# edp12.net
KiCad netlist of a schematic drawn in Altium Designer
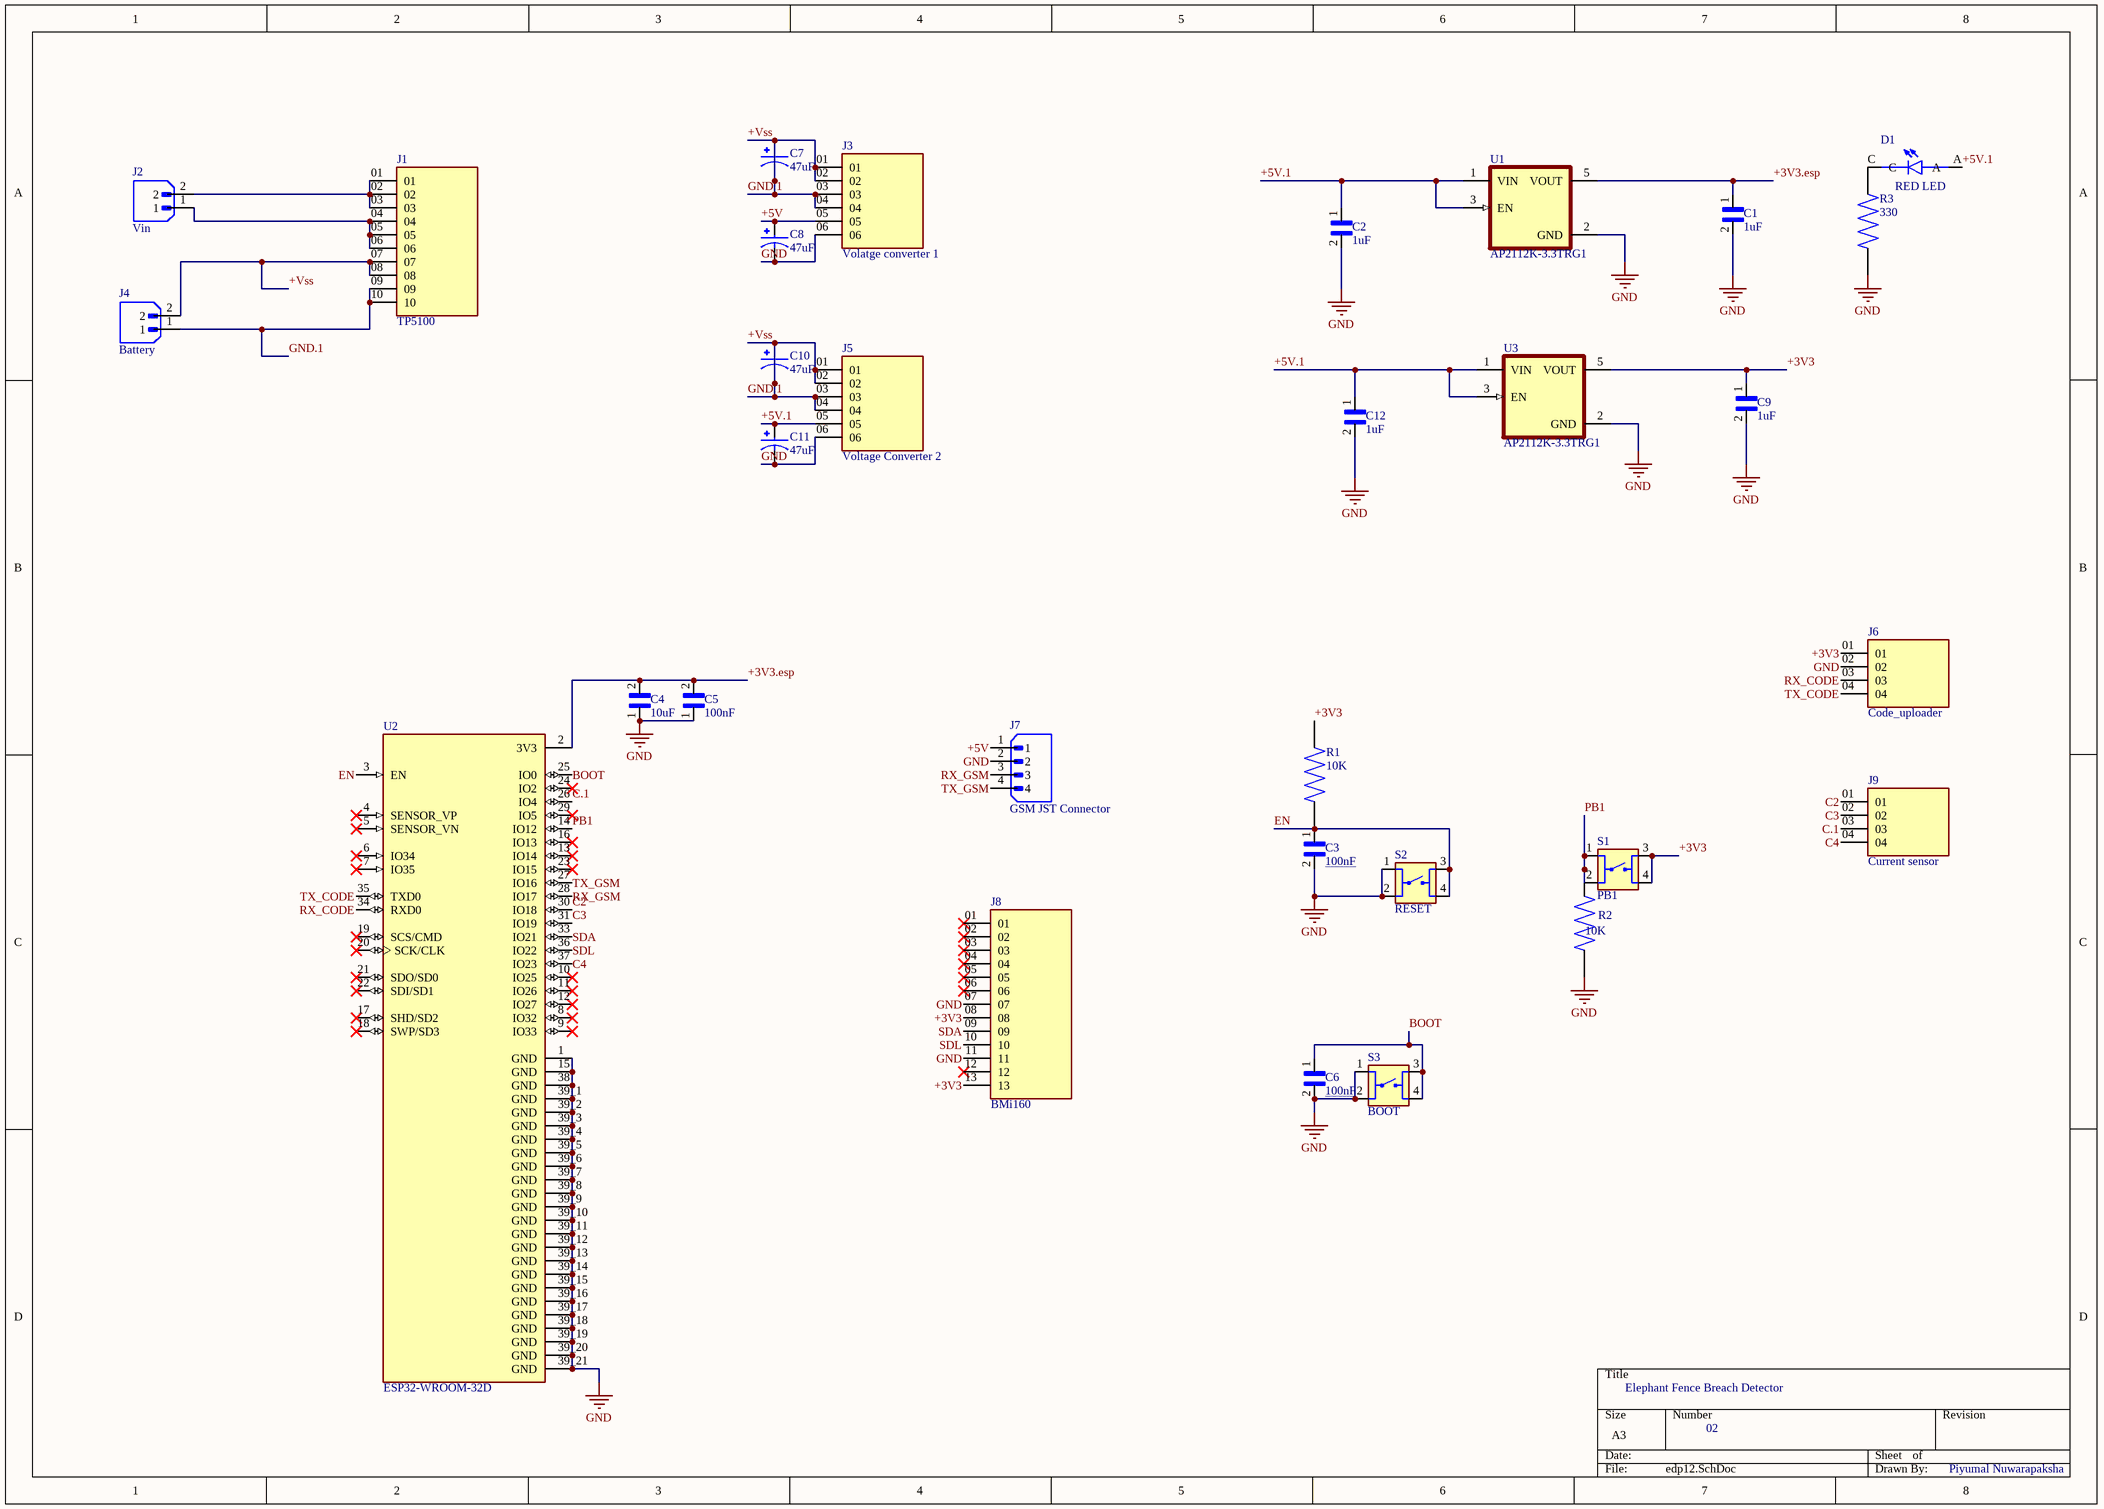
[diagram p0: edp12.SchDoc]

(export (version "E")
  (design (tool "Eeschema 10.0.6"))
  (components
    (comp (ref "C1")
      (value "1uF")
      (footprint "CAPC2012X135N")
      (description "Cap Ceramic 1uF 16V X7R 10% Pad SMD 0805 125C T/R")
      (fields (field (name "MP") "CL21B105KOFNNNE"))
      (libsource (lib "1uF") (part "CL21B105KOFNNNE"))
    )
    (comp (ref "C2")
      (value "1uF")
      (footprint "CAPC2012X135N")
      (description "Cap Ceramic 1uF 16V X7R 10% Pad SMD 0805 125C T/R")
      (fields (field (name "MP") "CL21B105KOFNNNE"))
      (libsource (lib "1uF") (part "CL21B105KOFNNNE"))
    )
    (comp (ref "C3")
      (value "CL31A106KBHNNNE")
      (footprint "CAPC2012X135N")
      (description "10ÂµF Â±10% 50V Ceramic Capacitor X5R 1206 (3216 Metric)")
      (fields (field (name "MF") "Samsung Electro-Mechanics") (field (name "ALTIUM_UNNAMED_1") "100nF"))
      (libsource (lib "10uF") (part "CL31A106KBHNNNE"))
    )
    (comp (ref "C4")
      (value "10uF")
      (footprint "CAPC2012X135N")
      (description "10ÂµF Â±10% 25V Ceramic Capacitor X5R 0805 (2012 Metric)")
      (fields (field (name "MF") "Samsung") (field (name "MP") "CL21A106KAYNNNE"))
      (libsource (lib "CL21A106KAYNNNE") (part "CL21A106KAYNNNE"))
    )
    (comp (ref "C5")
      (value "100nF")
      (footprint "CAPC2012X135N")
      (description "10ÂµF Â±10% 25V Ceramic Capacitor X5R 0805 (2012 Metric)")
      (fields (field (name "MF") "Samsung") (field (name "MP") "CL21A106KAYNNNE"))
      (libsource (lib "CL21A106KAYNNNE") (part "CL21A106KAYNNNE"))
    )
    (comp (ref "C6")
      (value "CL31A106KBHNNNE")
      (footprint "CAPC2012X135N")
      (description "10ÂµF Â±10% 50V Ceramic Capacitor X5R 1206 (3216 Metric)")
      (fields (field (name "MF") "Samsung Electro-Mechanics") (field (name "ALTIUM_UNNAMED_1") "100nF"))
      (libsource (lib "10uF") (part "CL31A106KBHNNNE"))
    )
    (comp (ref "C7")
      (value "47uF")
      (footprint "CAP_EEEFH1V470XL")
      (fields (field (name "MF") "Panasonic") (field (name "MP") "EEE-FH1V470XL"))
      (libsource (lib "47uF") (part "EEEFH1V470XL"))
    )
    (comp (ref "C8")
      (value "47uF")
      (footprint "CAP_EEEFH1V470XL")
      (fields (field (name "MF") "Panasonic") (field (name "MP") "EEE-FH1V470XL"))
      (libsource (lib "47uF") (part "EEEFH1V470XL"))
    )
    (comp (ref "C9")
      (value "1uF")
      (footprint "CAPC2012X135N")
      (description "Cap Ceramic 1uF 16V X7R 10% Pad SMD 0805 125C T/R")
      (fields (field (name "MP") "CL21B105KOFNNNE"))
      (libsource (lib "1uF") (part "CL21B105KOFNNNE"))
    )
    (comp (ref "C10")
      (value "47uF")
      (footprint "CAP_EEEFH1V470XL")
      (fields (field (name "MF") "Panasonic") (field (name "MP") "EEE-FH1V470XL"))
      (libsource (lib "47uF") (part "EEEFH1V470XL"))
    )
    (comp (ref "C11")
      (value "47uF")
      (footprint "CAP_EEEFH1V470XL")
      (fields (field (name "MF") "Panasonic") (field (name "MP") "EEE-FH1V470XL"))
      (libsource (lib "47uF") (part "EEEFH1V470XL"))
    )
    (comp (ref "C12")
      (value "1uF")
      (footprint "CAPC2012X135N")
      (description "Cap Ceramic 1uF 16V X7R 10% Pad SMD 0805 125C T/R")
      (fields (field (name "MP") "CL21B105KOFNNNE"))
      (libsource (lib "1uF") (part "CL21B105KOFNNNE"))
    )
    (comp (ref "D1")
      (value "RED LED")
      (footprint "LEDC2012X70N")
      (description "LED Uni-Color Green 4-Pin Chip 0805 T/R")
      (fields (field (name "MP") "597-3305-607F"))
      (libsource (lib "597-3305-607F (1)") (part "597-3305-607F"))
    )
    (comp (ref "J1")
      (value "TP5100")
      (footprint "SAMTEC_TS-121-G-AA")
      (description "Connector Header position")
      (fields (field (name "MP") "TS-121-G-AA") (field (name "MF") "Samtec"))
      (libsource (lib "power_header") (part "TS-121-G-AA"))
    )
    (comp (ref "J2")
      (value "Vin")
      (footprint "JST_B2B-XH-A(LF)(SN)")
      (description "Connector Header Through Hole 2 position 0.098 (2.50mm)")
      (fields (field (name "MF") "JST Sales") (field (name "MP") "B2B-XH-A(LF)(SN)"))
      (libsource (lib "B2B-XH-A_LF__SN_") (part "B2B-XH-A(LF)(SN)"))
    )
    (comp (ref "J3")
      (value "Volatge converter 1")
      (footprint "SAMTEC_TS-121-G-AA")
      (description "Connector Header position")
      (fields (field (name "MP") "TS-121-G-AA") (field (name "MF") "Samtec"))
      (libsource (lib "MD1584") (part "TS-121-G-AA"))
    )
    (comp (ref "J4")
      (value "Battery")
      (footprint "JST_B2B-XH-A(LF)(SN)")
      (description "Connector Header Through Hole 2 position 0.098 (2.50mm)")
      (fields (field (name "MF") "JST Sales") (field (name "MP") "B2B-XH-A(LF)(SN)"))
      (libsource (lib "B2B-XH-A_LF__SN_") (part "B2B-XH-A(LF)(SN)"))
    )
    (comp (ref "J5")
      (value "Voltage Converter 2")
      (footprint "SAMTEC_TS-121-G-AA")
      (description "Connector Header position")
      (fields (field (name "MP") "TS-121-G-AA") (field (name "MF") "Samtec"))
      (libsource (lib "MD1584") (part "TS-121-G-AA"))
    )
    (comp (ref "J6")
      (value "Code_uploader")
      (footprint "SAMTEC_TS-115-G-AA")
      (fields (field (name "MP") "TS-115-G-AA") (field (name "MF") "Samtec"))
      (libsource (lib "4pin_maleheader") (part "TS-115-G-AA"))
    )
    (comp (ref "J7")
      (value "GSM JST Connector")
      (footprint "JST_B4B-XH-A(LF)(SN)")
      (description "Connector Header Through Hole 4 position 0.098 (2.50mm)")
      (fields (field (name "MF") "JST Sales") (field (name "MP") "B4B-XH-A(LF)(SN)"))
      (libsource (lib "B4B-XH-A_LF__SN_") (part "B4B-XH-A(LF)(SN)"))
    )
    (comp (ref "J8")
      (value "BMi160")
      (footprint "SAMTEC_TS-115-G-AA")
      (fields (field (name "MP") "TS-115-G-AA") (field (name "MF") "Samtec"))
      (libsource (lib "BMImodule") (part "TS-115-G-AA"))
    )
    (comp (ref "J9")
      (value "Current sensor")
      (footprint "SAMTEC_TS-115-G-AA")
      (fields (field (name "MP") "TS-115-G-AA") (field (name "MF") "Samtec"))
      (libsource (lib "4pin_maleheader") (part "TS-115-G-AA"))
    )
    (comp (ref "R1")
      (value "10K")
      (footprint "RESC2012X60N")
      (description "10 kOhms Â±1% 0.125W, 1/8W Chip Resistor 0805 (2012 Metric) Moisture Resistant Thick Film")
      (fields (field (name "MF") "Yageo") (field (name "MP") "RC0805FR-0710KL"))
      (libsource (lib "10_k") (part "RC0805FR-0710KL"))
    )
    (comp (ref "R2")
      (value "10K")
      (footprint "RESC2012X60N")
      (description "10 kOhms Â±1% 0.125W, 1/8W Chip Resistor 0805 (2012 Metric) Moisture Resistant Thick Film")
      (fields (field (name "MF") "Yageo") (field (name "MP") "RC0805FR-0710KL"))
      (libsource (lib "10_k") (part "RC0805FR-0710KL"))
    )
    (comp (ref "R3")
      (value "330")
      (footprint "RESC2012X60N")
      (description "10 kOhms Â±1% 0.125W, 1/8W Chip Resistor 0805 (2012 Metric) Moisture Resistant Thick Film")
      (fields (field (name "MF") "Yageo") (field (name "MP") "RC0805FR-0710KL"))
      (libsource (lib "10_k") (part "RC0805FR-0710KL"))
    )
    (comp (ref "S1")
      (value "PB1")
      (footprint "SW_TS-1187A-B-A-B")
      (description "Tactile Switch SPST-NO Top Actuated Through Hole")
      (fields (field (name "MP") "FSM8JH") (field (name "MF") "TE Connectivity"))
      (libsource (lib "TS-1187A-B-A-B") (part "FSM8JH"))
    )
    (comp (ref "S2")
      (value "RESET")
      (footprint "SW_TS-1187A-B-A-B")
      (description "Tactile Switch SPST-NO Top Actuated Through Hole")
      (fields (field (name "MP") "FSM8JH") (field (name "MF") "TE Connectivity"))
      (libsource (lib "TS-1187A-B-A-B") (part "FSM8JH"))
    )
    (comp (ref "S3")
      (value "BOOT")
      (footprint "SW_TS-1187A-B-A-B")
      (description "Tactile Switch SPST-NO Top Actuated Through Hole")
      (fields (field (name "MP") "FSM8JH") (field (name "MF") "TE Connectivity"))
      (libsource (lib "TS-1187A-B-A-B") (part "FSM8JH"))
    )
    (comp (ref "U1")
      (value "AP2112K-3.3TRG1")
      (footprint "SOT95P285X140-5N")
      (description "Linear Voltage Regulator IC Positive Fixed 1 Output 600mA SOT-25")
      (fields (field (name "MF") "Diodes Inc."))
      (libsource (lib "AP2112K-3.3TRG1") (part "AP2112K-3.3TRG1"))
    )
    (comp (ref "U2")
      (value "ESP32-WROOM-32D")
      (footprint "MODULE_ESP32-WROOM-32D")
      (fields (field (name "MF") "Espressif Systems"))
      (libsource (lib "ESP32-WROOM-32D") (part "ESP32-WROOM-32D"))
    )
    (comp (ref "U3")
      (value "AP2112K-3.3TRG1")
      (footprint "SOT95P285X140-5N")
      (description "Linear Voltage Regulator IC Positive Fixed 1 Output 600mA SOT-25")
      (fields (field (name "MF") "Diodes Inc."))
      (libsource (lib "AP2112K-3.3TRG1") (part "AP2112K-3.3TRG1"))
    )
  )
  (nets
    (net (code "1") (name "/+3V3") (class "Default")
      (node (ref "C9") (pin "1") (pinfunction "1_1") (pintype "passive"))
      (node (ref "J6") (pin "01") (pinfunction "01_01") (pintype "passive"))
      (node (ref "J8") (pin "08") (pinfunction "08_08") (pintype "passive"))
      (node (ref "J8") (pin "13") (pinfunction "13_13") (pintype "passive"))
      (node (ref "R1") (pin "2") (pinfunction "2_2") (pintype "passive"))
      (node (ref "S1") (pin "3") (pinfunction "3_3") (pintype "passive"))
      (node (ref "S1") (pin "4") (pinfunction "4_4") (pintype "passive"))
      (node (ref "U3") (pin "5") (pinfunction "VOUT_5") (pintype "power_in"))
    )
    (net (code "2") (name "/+3V3.esp") (class "Default")
      (node (ref "C1") (pin "1") (pinfunction "1_1") (pintype "passive"))
      (node (ref "C4") (pin "2") (pinfunction "2_2") (pintype "passive"))
      (node (ref "C5") (pin "2") (pinfunction "2_2") (pintype "passive"))
      (node (ref "U1") (pin "5") (pinfunction "VOUT_5") (pintype "power_in"))
      (node (ref "U2") (pin "2") (pinfunction "3V3_2") (pintype "power_in"))
    )
    (net (code "3") (name "/+5V") (class "Default")
      (node (ref "C8") (pin "1") (pinfunction "1_1") (pintype "passive"))
      (node (ref "J3") (pin "05") (pinfunction "05_05") (pintype "passive"))
      (node (ref "J7") (pin "1") (pinfunction "1_1") (pintype "passive"))
    )
    (net (code "4") (name "/+5V.1") (class "Default")
      (node (ref "C11") (pin "1") (pinfunction "1_1") (pintype "passive"))
      (node (ref "C12") (pin "1") (pinfunction "1_1") (pintype "passive"))
      (node (ref "C2") (pin "1") (pinfunction "1_1") (pintype "passive"))
      (node (ref "D1") (pin "A") (pinfunction "A_A") (pintype "passive"))
      (node (ref "J5") (pin "05") (pinfunction "05_05") (pintype "passive"))
      (node (ref "U1") (pin "1") (pinfunction "VIN_1") (pintype "power_in"))
      (node (ref "U1") (pin "3") (pinfunction "EN_3") (pintype "input"))
      (node (ref "U3") (pin "1") (pinfunction "VIN_1") (pintype "power_in"))
      (node (ref "U3") (pin "3") (pinfunction "EN_3") (pintype "input"))
    )
    (net (code "5") (name "/+Vss") (class "Default")
      (node (ref "C10") (pin "1") (pinfunction "1_1") (pintype "passive"))
      (node (ref "C10") (pin "2") (pinfunction "2_2") (pintype "passive"))
      (node (ref "C7") (pin "1") (pinfunction "1_1") (pintype "passive"))
      (node (ref "C7") (pin "2") (pinfunction "2_2") (pintype "passive"))
      (node (ref "J1") (pin "07") (pinfunction "07_07") (pintype "passive"))
      (node (ref "J1") (pin "08") (pinfunction "08_08") (pintype "passive"))
      (node (ref "J1") (pin "09") (pinfunction "09_09") (pintype "passive"))
      (node (ref "J1") (pin "10") (pinfunction "10_10") (pintype "passive"))
      (node (ref "J3") (pin "01") (pinfunction "01_01") (pintype "passive"))
      (node (ref "J3") (pin "02") (pinfunction "02_02") (pintype "passive"))
      (node (ref "J3") (pin "03") (pinfunction "03_03") (pintype "passive"))
      (node (ref "J3") (pin "04") (pinfunction "04_04") (pintype "passive"))
      (node (ref "J4") (pin "1") (pinfunction "1_1") (pintype "passive"))
      (node (ref "J4") (pin "2") (pinfunction "2_2") (pintype "passive"))
      (node (ref "J5") (pin "01") (pinfunction "01_01") (pintype "passive"))
      (node (ref "J5") (pin "02") (pinfunction "02_02") (pintype "passive"))
      (node (ref "J5") (pin "03") (pinfunction "03_03") (pintype "passive"))
      (node (ref "J5") (pin "04") (pinfunction "04_04") (pintype "passive"))
    )
    (net (code "6") (name "/BOOT") (class "Default")
      (node (ref "C6") (pin "1") (pinfunction "1_1") (pintype "passive"))
      (node (ref "S3") (pin "3") (pinfunction "3_3") (pintype "passive"))
      (node (ref "S3") (pin "4") (pinfunction "4_4") (pintype "passive"))
      (node (ref "U2") (pin "25") (pinfunction "IO0_25") (pintype "bidirectional"))
    )
    (net (code "7") (name "/C.1") (class "Default")
      (node (ref "J9") (pin "03") (pinfunction "03_03") (pintype "passive"))
      (node (ref "U2") (pin "26") (pinfunction "IO4_26") (pintype "bidirectional"))
    )
    (net (code "8") (name "/C2") (class "Default")
      (node (ref "J9") (pin "01") (pinfunction "01_01") (pintype "passive"))
      (node (ref "U2") (pin "30") (pinfunction "IO18_30") (pintype "bidirectional"))
    )
    (net (code "9") (name "/C3") (class "Default")
      (node (ref "J9") (pin "02") (pinfunction "02_02") (pintype "passive"))
      (node (ref "U2") (pin "31") (pinfunction "IO19_31") (pintype "bidirectional"))
    )
    (net (code "10") (name "/C4") (class "Default")
      (node (ref "J9") (pin "04") (pinfunction "04_04") (pintype "passive"))
      (node (ref "U2") (pin "37") (pinfunction "IO23_37") (pintype "bidirectional"))
    )
    (net (code "11") (name "/EN") (class "Default")
      (node (ref "C3") (pin "1") (pinfunction "1_1") (pintype "passive"))
      (node (ref "R1") (pin "1") (pinfunction "1_1") (pintype "passive"))
      (node (ref "S2") (pin "3") (pinfunction "3_3") (pintype "passive"))
      (node (ref "S2") (pin "4") (pinfunction "4_4") (pintype "passive"))
      (node (ref "U2") (pin "3") (pinfunction "EN_3") (pintype "input"))
    )
    (net (code "12") (name "/PB1") (class "Default")
      (node (ref "R2") (pin "2") (pinfunction "2_2") (pintype "passive"))
      (node (ref "S1") (pin "1") (pinfunction "1_1") (pintype "passive"))
      (node (ref "S1") (pin "2") (pinfunction "2_2") (pintype "passive"))
      (node (ref "U2") (pin "14") (pinfunction "IO12_14") (pintype "bidirectional"))
    )
    (net (code "13") (name "/RX_CODE") (class "Default")
      (node (ref "J6") (pin "03") (pinfunction "03_03") (pintype "passive"))
      (node (ref "U2") (pin "34") (pinfunction "RXD0_34") (pintype "bidirectional"))
    )
    (net (code "14") (name "/RX_GSM") (class "Default")
      (node (ref "J7") (pin "3") (pinfunction "3_3") (pintype "passive"))
      (node (ref "U2") (pin "28") (pinfunction "IO17_28") (pintype "bidirectional"))
    )
    (net (code "15") (name "/SDA") (class "Default")
      (node (ref "J8") (pin "09") (pinfunction "09_09") (pintype "passive"))
      (node (ref "U2") (pin "33") (pinfunction "IO21_33") (pintype "bidirectional"))
    )
    (net (code "16") (name "/SDL") (class "Default")
      (node (ref "J8") (pin "10") (pinfunction "10_10") (pintype "passive"))
      (node (ref "U2") (pin "36") (pinfunction "IO22_36") (pintype "bidirectional"))
    )
    (net (code "17") (name "/TX_CODE") (class "Default")
      (node (ref "J6") (pin "04") (pinfunction "04_04") (pintype "passive"))
      (node (ref "U2") (pin "35") (pinfunction "TXD0_35") (pintype "bidirectional"))
    )
    (net (code "18") (name "/TX_GSM") (class "Default")
      (node (ref "J7") (pin "4") (pinfunction "4_4") (pintype "passive"))
      (node (ref "U2") (pin "27") (pinfunction "IO16_27") (pintype "bidirectional"))
    )
    (net (code "19") (name "GND") (class "Default")
      (node (ref "C1") (pin "2") (pinfunction "2_2") (pintype "passive"))
      (node (ref "C11") (pin "2") (pinfunction "2_2") (pintype "passive"))
      (node (ref "C12") (pin "2") (pinfunction "2_2") (pintype "passive"))
      (node (ref "C2") (pin "2") (pinfunction "2_2") (pintype "passive"))
      (node (ref "C3") (pin "2") (pinfunction "2_2") (pintype "passive"))
      (node (ref "C4") (pin "1") (pinfunction "1_1") (pintype "passive"))
      (node (ref "C5") (pin "1") (pinfunction "1_1") (pintype "passive"))
      (node (ref "C6") (pin "2") (pinfunction "2_2") (pintype "passive"))
      (node (ref "C8") (pin "2") (pinfunction "2_2") (pintype "passive"))
      (node (ref "C9") (pin "2") (pinfunction "2_2") (pintype "passive"))
      (node (ref "J3") (pin "06") (pinfunction "06_06") (pintype "passive"))
      (node (ref "J5") (pin "06") (pinfunction "06_06") (pintype "passive"))
      (node (ref "J6") (pin "02") (pinfunction "02_02") (pintype "passive"))
      (node (ref "J7") (pin "2") (pinfunction "2_2") (pintype "passive"))
      (node (ref "J8") (pin "07") (pinfunction "07_07") (pintype "passive"))
      (node (ref "J8") (pin "11") (pinfunction "11_11") (pintype "passive"))
      (node (ref "R2") (pin "1") (pinfunction "1_1") (pintype "passive"))
      (node (ref "R3") (pin "1") (pinfunction "1_1") (pintype "passive"))
      (node (ref "S2") (pin "1") (pinfunction "1_1") (pintype "passive"))
      (node (ref "S2") (pin "2") (pinfunction "2_2") (pintype "passive"))
      (node (ref "S3") (pin "1") (pinfunction "1_1") (pintype "passive"))
      (node (ref "S3") (pin "2") (pinfunction "2_2") (pintype "passive"))
      (node (ref "U1") (pin "2") (pinfunction "GND_2") (pintype "power_in"))
      (node (ref "U2") (pin "1") (pinfunction "GND_1") (pintype "power_in"))
      (node (ref "U2") (pin "15") (pinfunction "GND_15") (pintype "power_in"))
      (node (ref "U2") (pin "38") (pinfunction "GND_38") (pintype "power_in"))
      (node (ref "U2") (pin "39_1") (pinfunction "GND_39_1") (pintype "power_in"))
      (node (ref "U2") (pin "39_10") (pinfunction "GND_39_10") (pintype "power_in"))
      (node (ref "U2") (pin "39_11") (pinfunction "GND_39_11") (pintype "power_in"))
      (node (ref "U2") (pin "39_12") (pinfunction "GND_39_12") (pintype "power_in"))
      (node (ref "U2") (pin "39_13") (pinfunction "GND_39_13") (pintype "power_in"))
      (node (ref "U2") (pin "39_14") (pinfunction "GND_39_14") (pintype "power_in"))
      (node (ref "U2") (pin "39_15") (pinfunction "GND_39_15") (pintype "power_in"))
      (node (ref "U2") (pin "39_16") (pinfunction "GND_39_16") (pintype "power_in"))
      (node (ref "U2") (pin "39_17") (pinfunction "GND_39_17") (pintype "power_in"))
      (node (ref "U2") (pin "39_18") (pinfunction "GND_39_18") (pintype "power_in"))
      (node (ref "U2") (pin "39_19") (pinfunction "GND_39_19") (pintype "power_in"))
      (node (ref "U2") (pin "39_2") (pinfunction "GND_39_2") (pintype "power_in"))
      (node (ref "U2") (pin "39_20") (pinfunction "GND_39_20") (pintype "power_in"))
      (node (ref "U2") (pin "39_21") (pinfunction "GND_39_21") (pintype "power_in"))
      (node (ref "U2") (pin "39_3") (pinfunction "GND_39_3") (pintype "power_in"))
      (node (ref "U2") (pin "39_4") (pinfunction "GND_39_4") (pintype "power_in"))
      (node (ref "U2") (pin "39_5") (pinfunction "GND_39_5") (pintype "power_in"))
      (node (ref "U2") (pin "39_6") (pinfunction "GND_39_6") (pintype "power_in"))
      (node (ref "U2") (pin "39_7") (pinfunction "GND_39_7") (pintype "power_in"))
      (node (ref "U2") (pin "39_8") (pinfunction "GND_39_8") (pintype "power_in"))
      (node (ref "U2") (pin "39_9") (pinfunction "GND_39_9") (pintype "power_in"))
      (node (ref "U3") (pin "2") (pinfunction "GND_2") (pintype "power_in"))
    )
    (net (code "20") (name "Net-(D1-PadC)") (class "Default")
      (node (ref "D1") (pin "C") (pinfunction "C_C") (pintype "passive"))
      (node (ref "R3") (pin "2") (pinfunction "2_2") (pintype "passive"))
    )
    (net (code "21") (name "Net-(J1-Pad01)") (class "Default")
      (node (ref "J1") (pin "01") (pinfunction "01_01") (pintype "passive"))
      (node (ref "J1") (pin "02") (pinfunction "02_02") (pintype "passive"))
      (node (ref "J1") (pin "03") (pinfunction "03_03") (pintype "passive"))
      (node (ref "J2") (pin "2") (pinfunction "2_2") (pintype "passive"))
    )
    (net (code "22") (name "Net-(J1-Pad04)") (class "Default")
      (node (ref "J1") (pin "04") (pinfunction "04_04") (pintype "passive"))
      (node (ref "J1") (pin "05") (pinfunction "05_05") (pintype "passive"))
      (node (ref "J1") (pin "06") (pinfunction "06_06") (pintype "passive"))
      (node (ref "J2") (pin "1") (pinfunction "1_1") (pintype "passive"))
    )
    (net (code "23") (name "unconnected-(J8-Pad01)") (class "Default")
      (node (ref "J8") (pin "01") (pinfunction "01_01") (pintype "passive+no_connect"))
    )
    (net (code "24") (name "unconnected-(J8-Pad02)") (class "Default")
      (node (ref "J8") (pin "02") (pinfunction "02_02") (pintype "passive+no_connect"))
    )
    (net (code "25") (name "unconnected-(J8-Pad03)") (class "Default")
      (node (ref "J8") (pin "03") (pinfunction "03_03") (pintype "passive+no_connect"))
    )
    (net (code "26") (name "unconnected-(J8-Pad04)") (class "Default")
      (node (ref "J8") (pin "04") (pinfunction "04_04") (pintype "passive+no_connect"))
    )
    (net (code "27") (name "unconnected-(J8-Pad05)") (class "Default")
      (node (ref "J8") (pin "05") (pinfunction "05_05") (pintype "passive+no_connect"))
    )
    (net (code "28") (name "unconnected-(J8-Pad06)") (class "Default")
      (node (ref "J8") (pin "06") (pinfunction "06_06") (pintype "passive+no_connect"))
    )
    (net (code "29") (name "unconnected-(J8-Pad12)") (class "Default")
      (node (ref "J8") (pin "12") (pinfunction "12_12") (pintype "passive+no_connect"))
    )
    (net (code "30") (name "unconnected-(U2-IO2-Pad24)") (class "Default")
      (node (ref "U2") (pin "24") (pinfunction "IO2_24") (pintype "bidirectional+no_connect"))
    )
    (net (code "31") (name "unconnected-(U2-IO5-Pad29)") (class "Default")
      (node (ref "U2") (pin "29") (pinfunction "IO5_29") (pintype "bidirectional+no_connect"))
    )
    (net (code "32") (name "unconnected-(U2-IO13-Pad16)") (class "Default")
      (node (ref "U2") (pin "16") (pinfunction "IO13_16") (pintype "bidirectional+no_connect"))
    )
    (net (code "33") (name "unconnected-(U2-IO14-Pad13)") (class "Default")
      (node (ref "U2") (pin "13") (pinfunction "IO14_13") (pintype "bidirectional+no_connect"))
    )
    (net (code "34") (name "unconnected-(U2-IO15-Pad23)") (class "Default")
      (node (ref "U2") (pin "23") (pinfunction "IO15_23") (pintype "bidirectional+no_connect"))
    )
    (net (code "35") (name "unconnected-(U2-IO25-Pad10)") (class "Default")
      (node (ref "U2") (pin "10") (pinfunction "IO25_10") (pintype "bidirectional+no_connect"))
    )
    (net (code "36") (name "unconnected-(U2-IO26-Pad11)") (class "Default")
      (node (ref "U2") (pin "11") (pinfunction "IO26_11") (pintype "bidirectional+no_connect"))
    )
    (net (code "37") (name "unconnected-(U2-IO27-Pad12)") (class "Default")
      (node (ref "U2") (pin "12") (pinfunction "IO27_12") (pintype "bidirectional+no_connect"))
    )
    (net (code "38") (name "unconnected-(U2-IO32-Pad8)") (class "Default")
      (node (ref "U2") (pin "8") (pinfunction "IO32_8") (pintype "bidirectional+no_connect"))
    )
    (net (code "39") (name "unconnected-(U2-IO33-Pad9)") (class "Default")
      (node (ref "U2") (pin "9") (pinfunction "IO33_9") (pintype "bidirectional+no_connect"))
    )
    (net (code "40") (name "unconnected-(U2-IO34-Pad6)") (class "Default")
      (node (ref "U2") (pin "6") (pinfunction "IO34_6") (pintype "input+no_connect"))
    )
    (net (code "41") (name "unconnected-(U2-IO35-Pad7)") (class "Default")
      (node (ref "U2") (pin "7") (pinfunction "IO35_7") (pintype "input+no_connect"))
    )
    (net (code "42") (name "unconnected-(U2-SCK{slash}CLK-Pad20)") (class "Default")
      (node (ref "U2") (pin "20") (pinfunction "SCK/CLK_20") (pintype "bidirectional+no_connect"))
    )
    (net (code "43") (name "unconnected-(U2-SCS{slash}CMD-Pad19)") (class "Default")
      (node (ref "U2") (pin "19") (pinfunction "SCS/CMD_19") (pintype "bidirectional+no_connect"))
    )
    (net (code "44") (name "unconnected-(U2-SDI{slash}SD1-Pad22)") (class "Default")
      (node (ref "U2") (pin "22") (pinfunction "SDI/SD1_22") (pintype "bidirectional+no_connect"))
    )
    (net (code "45") (name "unconnected-(U2-SDO{slash}SD0-Pad21)") (class "Default")
      (node (ref "U2") (pin "21") (pinfunction "SDO/SD0_21") (pintype "bidirectional+no_connect"))
    )
    (net (code "46") (name "unconnected-(U2-SENSOR_VN-Pad5)") (class "Default")
      (node (ref "U2") (pin "5") (pinfunction "SENSOR_VN_5") (pintype "input+no_connect"))
    )
    (net (code "47") (name "unconnected-(U2-SENSOR_VP-Pad4)") (class "Default")
      (node (ref "U2") (pin "4") (pinfunction "SENSOR_VP_4") (pintype "input+no_connect"))
    )
    (net (code "48") (name "unconnected-(U2-SHD{slash}SD2-Pad17)") (class "Default")
      (node (ref "U2") (pin "17") (pinfunction "SHD/SD2_17") (pintype "bidirectional+no_connect"))
    )
    (net (code "49") (name "unconnected-(U2-SWP{slash}SD3-Pad18)") (class "Default")
      (node (ref "U2") (pin "18") (pinfunction "SWP/SD3_18") (pintype "bidirectional+no_connect"))
    )
  )
)
